# Display.net
KiCad netlist of a schematic drawn in Altium Designer
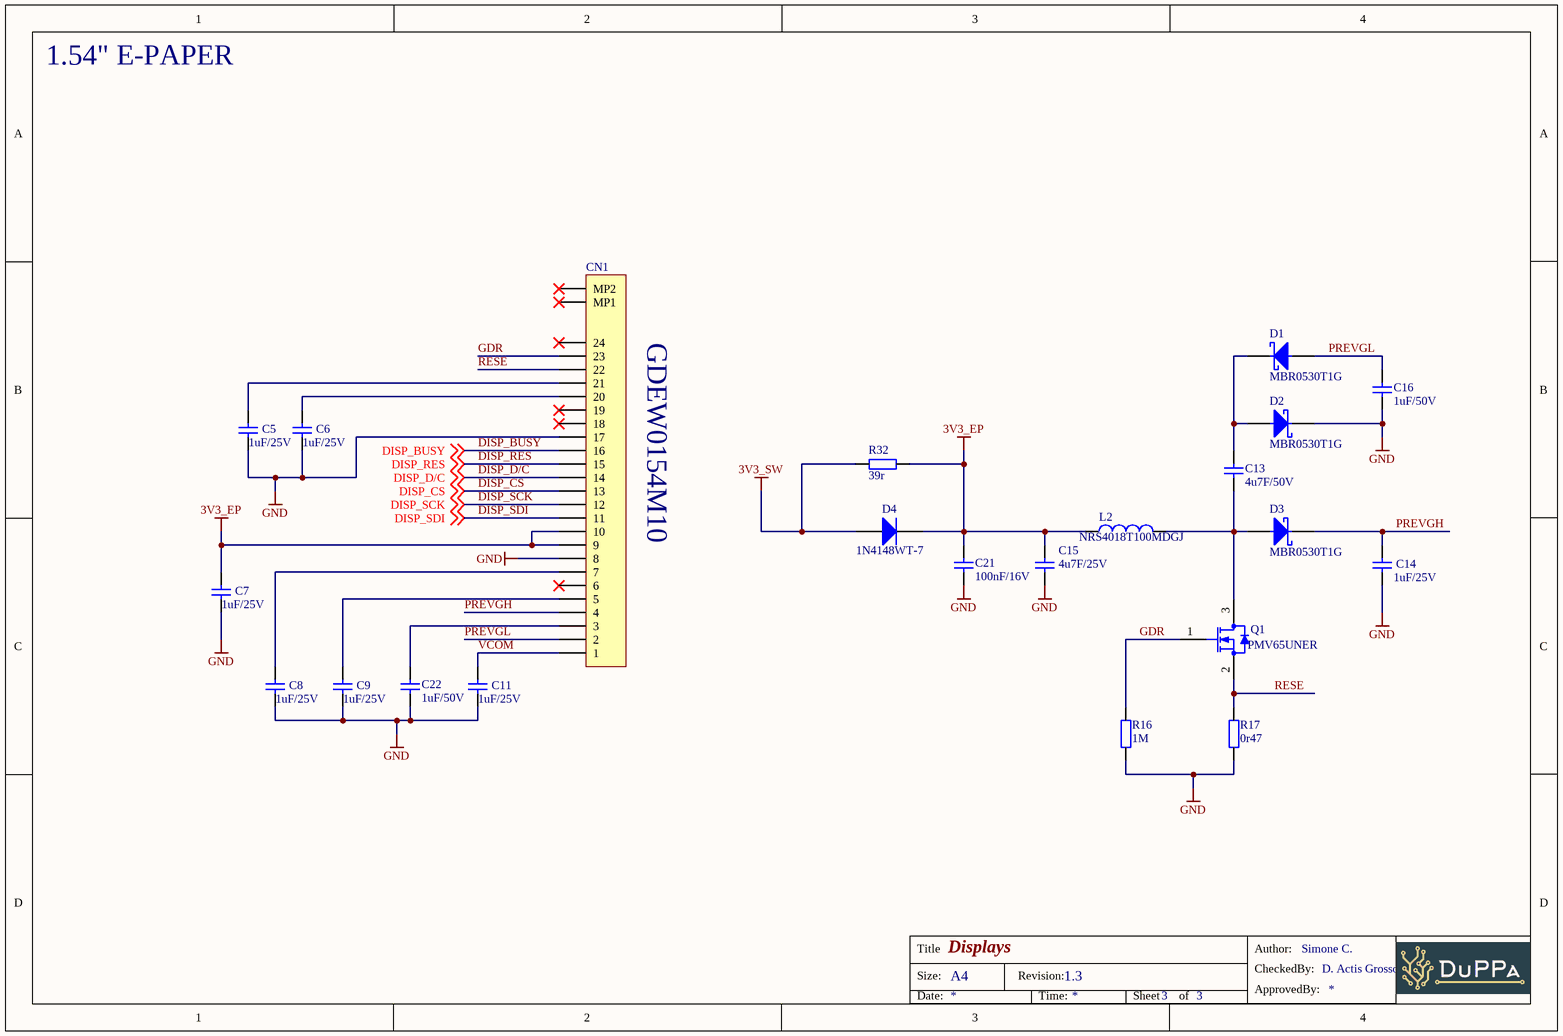
[diagram p0: Display.SchDoc]

(export (version "E")
  (design (tool "Eeschema 10.0.6"))
  (components
    (comp (ref "C5")
      (value "1uF/25V")
      (footprint "C0402")
      (description "1uF ±10% 25V Ceramic Capacitor X5R 0402")
      (fields
        (field (name "PARTNUMBER") "CL05A105KA5NQNC")
        (field (name "MANUFACTURER") "Samsung Electro-Mechanics")
      )
      (libsource (lib "DuPPa_Lib") (part "Cap_0402_1uF/25V"))
    )
    (comp (ref "C6")
      (value "1uF/25V")
      (footprint "C0402")
      (description "1uF ±10% 25V Ceramic Capacitor X5R 0402")
      (fields
        (field (name "PARTNUMBER") "CL05A105KA5NQNC")
        (field (name "MANUFACTURER") "Samsung Electro-Mechanics")
      )
      (libsource (lib "DuPPa_Lib") (part "Cap_0402_1uF/25V"))
    )
    (comp (ref "C7")
      (value "1uF/25V")
      (footprint "C0402")
      (description "1uF ±10% 25V Ceramic Capacitor X5R 0402")
      (fields
        (field (name "PARTNUMBER") "CL05A105KA5NQNC")
        (field (name "MANUFACTURER") "Samsung Electro-Mechanics")
      )
      (libsource (lib "DuPPa_Lib") (part "Cap_0402_1uF/25V"))
    )
    (comp (ref "C8")
      (value "1uF/25V")
      (footprint "C0402")
      (description "1uF ±10% 25V Ceramic Capacitor X5R 0402")
      (fields
        (field (name "PARTNUMBER") "CL05A105KA5NQNC")
        (field (name "MANUFACTURER") "Samsung Electro-Mechanics")
      )
      (libsource (lib "DuPPa_Lib") (part "Cap_0402_1uF/25V"))
    )
    (comp (ref "C9")
      (value "1uF/25V")
      (footprint "C0402")
      (description "1uF ±10% 25V Ceramic Capacitor X5R 0402")
      (fields
        (field (name "PARTNUMBER") "CL05A105KA5NQNC")
        (field (name "MANUFACTURER") "Samsung Electro-Mechanics")
      )
      (libsource (lib "DuPPa_Lib") (part "Cap_0402_1uF/25V"))
    )
    (comp (ref "C11")
      (value "1uF/25V")
      (footprint "C0402")
      (description "1uF ±10% 25V Ceramic Capacitor X5R 0402")
      (fields
        (field (name "PARTNUMBER") "CL05A105KA5NQNC")
        (field (name "MANUFACTURER") "Samsung Electro-Mechanics")
      )
      (libsource (lib "DuPPa_Lib") (part "Cap_0402_1uF/25V"))
    )
    (comp (ref "C13")
      (value "4u7F/50V")
      (footprint "C0805")
      (description "4.7uF ±10% 50V Ceramic Capacitor X5R 0805")
      (fields (field (name "PARTNUMBER") "HGC0805R5475K500NSLJ") (field (name "Comment") "Cap_0805_4u7F/50V"))
      (libsource (lib "DuPPa_Lib") (part "Cap_0805_4u7F/50V"))
    )
    (comp (ref "C14")
      (value "1uF/25V")
      (footprint "C0402")
      (description "1uF ±10% 25V Ceramic Capacitor X5R 0402")
      (fields
        (field (name "PARTNUMBER") "CL05A105KA5NQNC")
        (field (name "MANUFACTURER") "Samsung Electro-Mechanics")
      )
      (libsource (lib "DuPPa_Lib") (part "Cap_0402_1uF/25V"))
    )
    (comp (ref "C15")
      (value "4u7F/25V")
      (footprint "C0603")
      (description "4.7uF ±10% 35V Ceramic Capacitor X5R 0603")
      (fields
        (field (name "PARTNUMBER") "CL10A475KL8NRNC")
        (field (name "MANUFACTURER") "Samsung Electro-Mechanics")
      )
      (libsource (lib "DuPPa_Lib") (part "Cap_0603_4u7F/35V"))
    )
    (comp (ref "C16")
      (value "1uF/50V")
      (footprint "C0603")
      (description "50V 1uF X5R ±10% 0603 Ceramic Capacitors ROHS")
      (fields
        (field (name "PARTNUMBER") "CL10A105KB8NNNC")
        (field (name "MANUFACTURER") "Samsung Electro-Mechanics")
      )
      (libsource (lib "DuPPa_Lib") (part "Cap_0603_1uF/50V"))
    )
    (comp (ref "C21")
      (value "100nF/16V")
      (footprint "C0402")
      (description "16V 100nF X7R ±10% 0402 Multilayer Ceramic Capacitors MLCC - SMD/SMT ROHS")
      (fields
        (field (name "PARTNUMBER") "CL05B104KO5NNNC")
        (field (name "MANUFACTURER") "Samsung Electro-Mechanics")
      )
      (libsource (lib "DuPPa_Lib") (part "Cap_0402_100n/16V"))
    )
    (comp (ref "C22")
      (value "1uF/50V")
      (footprint "C0603")
      (description "50V 1uF X5R ±10% 0603 Ceramic Capacitors ROHS")
      (fields
        (field (name "PARTNUMBER") "CL10A105KB8NNNC")
        (field (name "MANUFACTURER") "Samsung Electro-Mechanics")
      )
      (libsource (lib "DuPPa_Lib") (part "Cap_0603_1uF/50V"))
    )
    (comp (ref "CN1")
      (value "F3311A7H121024E200")
      (footprint "F3311A7H121024E200")
      (fields (field (name "MANUFACTURER") "Amphenol ICC / FCI"))
      (libsource (lib "DuPPa_Lib") (part "F3311A7H121024E200"))
    )
    (comp (ref "D1")
      (value "MBR0530T1G")
      (footprint "FP-SOD123-MFG")
      (description "Diode 30V 500mA Surface Mount SOD-123")
      (fields (field (name "PARTNUMBER") "MBR0530T1G") (field (name "MANUFACTURER") "Onsemi"))
      (libsource (lib "DuPPa_Lib") (part "MBR0530T1G"))
    )
    (comp (ref "D2")
      (value "MBR0530T1G")
      (footprint "FP-SOD123-MFG")
      (description "Diode 30V 500mA Surface Mount SOD-123")
      (fields (field (name "PARTNUMBER") "MBR0530T1G") (field (name "MANUFACTURER") "Onsemi"))
      (libsource (lib "DuPPa_Lib") (part "MBR0530T1G"))
    )
    (comp (ref "D3")
      (value "MBR0530T1G")
      (footprint "FP-SOD123-MFG")
      (description "Diode 30V 500mA Surface Mount SOD-123")
      (fields (field (name "PARTNUMBER") "MBR0530T1G") (field (name "MANUFACTURER") "Onsemi"))
      (libsource (lib "DuPPa_Lib") (part "MBR0530T1G"))
    )
    (comp (ref "D4")
      (value "Diode_1N4148WT")
      (footprint "SODFL160X65-2N")
      (description "Diode Independent 80V 125mA Surface Mount SOD-523")
      (fields (field (name "PARTNUMBER") "1N4148WT-7") (field (name "MANUFACTURER") "Diodes"))
      (libsource (lib "DuPPa_Lib") (part "Diode_1N4148WT"))
    )
    (comp (ref "L2")
      (value "10uH_1.44A_NRS4018T100MDGJ")
      (footprint "FP-NRS4018-MFG")
      (description "1.2A 10uH ±20% 1.3A 150mΩ SMD,4x4mm Fixed Inductors RoHS")
      (fields (field (name "MANUFACTURER") "Taiyo Yuden") (field (name "PART NUMBER") "NRS4018T100MDGJ"))
      (libsource (lib "DuPPa_Lib") (part "10uH_1.44A_NRS4018T100MDGJ"))
    )
    (comp (ref "Q1")
      (value "PMV65UNER")
      (footprint "SOT-23-3")
      (description "N-Channel 20V 2.8A 940mW Surface Mount SOT-23")
      (fields (field (name "MANUFACTURER") "Nexperia"))
      (libsource (lib "DuPPa_Lib") (part "PMV65UNER"))
    )
    (comp (ref "R16")
      (value "1M")
      (footprint "R0402")
      (description "1MΩ ±1% 62.5mW 0402 Thick Film Resistor")
      (fields (field (name "PARTNUMBER") "0402WGF1004TCE") (field (name "MANUFACTURER") "UNI-ROYAL"))
      (libsource (lib "DuPPa_Lib") (part "R_R0402_1M"))
    )
    (comp (ref "R17")
      (value "0r47")
      (footprint "R0402")
      (description "0402, 1% ,63mW")
      (fields (field (name "PARTNUMBER") "RL0402JR-070R47L") (field (name "Comment") "R_R0402_0r47"))
      (libsource (lib "DuPPa_Lib") (part "R_R0402_0r47"))
    )
    (comp (ref "R32")
      (value "39r")
      (footprint "R0402")
      (description "39Ω ±1% 62.5mW 0402 Thick Film Resistor")
      (fields (field (name "PARTNUMBER") "0402WGF390JTCE") (field (name "MANUFACTURER") "UNI-ROYAL"))
      (libsource (lib "DuPPa_Lib") (part "R_R0402_39r"))
    )
  )
  (nets
    (net (code "1") (name "/GDR") (class "Default")
      (node (ref "CN1") (pin "23") (pinfunction "23_23") (pintype "passive"))
      (node (ref "Q1") (pin "1") (pinfunction "G_1") (pintype "passive"))
      (node (ref "R16") (pin "2") (pinfunction "2_2") (pintype "passive"))
    )
    (net (code "2") (name "/PREVGH") (class "Default")
      (node (ref "C14") (pin "1") (pinfunction "1_1") (pintype "passive"))
      (node (ref "CN1") (pin "4") (pinfunction "4_4") (pintype "passive"))
      (node (ref "D3") (pin "K") (pinfunction "K_K") (pintype "passive"))
    )
    (net (code "3") (name "/PREVGL") (class "Default")
      (node (ref "C16") (pin "1") (pinfunction "1_1") (pintype "passive"))
      (node (ref "CN1") (pin "2") (pinfunction "2_2") (pintype "passive"))
      (node (ref "D1") (pin "A") (pinfunction "A_A") (pintype "passive"))
    )
    (net (code "4") (name "/RESE") (class "Default")
      (node (ref "CN1") (pin "22") (pinfunction "22_22") (pintype "passive"))
      (node (ref "Q1") (pin "2") (pinfunction "S_2") (pintype "passive"))
      (node (ref "R17") (pin "2") (pinfunction "2_2") (pintype "passive"))
    )
    (net (code "5") (name "/VCOM") (class "Default")
      (node (ref "C11") (pin "1") (pinfunction "1_1") (pintype "passive"))
      (node (ref "CN1") (pin "1") (pinfunction "1_1") (pintype "passive"))
    )
    (net (code "6") (name "3V3_EP") (class "Default")
      (node (ref "C15") (pin "1") (pinfunction "1_1") (pintype "passive"))
      (node (ref "C21") (pin "1") (pinfunction "1_1") (pintype "passive"))
      (node (ref "C7") (pin "1") (pinfunction "1_1") (pintype "passive"))
      (node (ref "CN1") (pin "10") (pinfunction "10_10") (pintype "passive"))
      (node (ref "CN1") (pin "9") (pinfunction "9_9") (pintype "passive"))
      (node (ref "D4") (pin "K") (pinfunction "K_K") (pintype "passive"))
      (node (ref "L2") (pin "1") (pinfunction "1_1") (pintype "passive"))
      (node (ref "R32") (pin "2") (pinfunction "2_2") (pintype "passive"))
    )
    (net (code "7") (name "3V3_SW") (class "Default")
      (node (ref "D4") (pin "A") (pinfunction "A_A") (pintype "passive"))
      (node (ref "R32") (pin "1") (pinfunction "1_1") (pintype "passive"))
    )
    (net (code "8") (name "DISP_BUSY") (class "Default")
      (node (ref "CN1") (pin "16") (pinfunction "16_16") (pintype "passive"))
    )
    (net (code "9") (name "DISP_CS") (class "Default")
      (node (ref "CN1") (pin "13") (pinfunction "13_13") (pintype "passive"))
    )
    (net (code "10") (name "DISP_D{slash}C") (class "Default")
      (node (ref "CN1") (pin "14") (pinfunction "14_14") (pintype "passive"))
    )
    (net (code "11") (name "DISP_RES") (class "Default")
      (node (ref "CN1") (pin "15") (pinfunction "15_15") (pintype "passive"))
    )
    (net (code "12") (name "DISP_SCK") (class "Default")
      (node (ref "CN1") (pin "12") (pinfunction "12_12") (pintype "passive"))
    )
    (net (code "13") (name "DISP_SDI") (class "Default")
      (node (ref "CN1") (pin "11") (pinfunction "11_11") (pintype "passive"))
    )
    (net (code "14") (name "GND") (class "Default")
      (node (ref "C11") (pin "2") (pinfunction "2_2") (pintype "passive"))
      (node (ref "C14") (pin "2") (pinfunction "2_2") (pintype "passive"))
      (node (ref "C15") (pin "2") (pinfunction "2_2") (pintype "passive"))
      (node (ref "C16") (pin "2") (pinfunction "2_2") (pintype "passive"))
      (node (ref "C21") (pin "2") (pinfunction "2_2") (pintype "passive"))
      (node (ref "C22") (pin "2") (pinfunction "2_2") (pintype "passive"))
      (node (ref "C5") (pin "2") (pinfunction "2_2") (pintype "passive"))
      (node (ref "C6") (pin "2") (pinfunction "2_2") (pintype "passive"))
      (node (ref "C7") (pin "2") (pinfunction "2_2") (pintype "passive"))
      (node (ref "C8") (pin "2") (pinfunction "2_2") (pintype "passive"))
      (node (ref "C9") (pin "2") (pinfunction "2_2") (pintype "passive"))
      (node (ref "CN1") (pin "17") (pinfunction "17_17") (pintype "passive"))
      (node (ref "CN1") (pin "8") (pinfunction "8_8") (pintype "passive"))
      (node (ref "D2") (pin "K") (pinfunction "K_K") (pintype "passive"))
      (node (ref "R16") (pin "1") (pinfunction "1_1") (pintype "passive"))
      (node (ref "R17") (pin "1") (pinfunction "1_1") (pintype "passive"))
    )
    (net (code "15") (name "Net-(C5-Pad1)") (class "Default")
      (node (ref "C5") (pin "1") (pinfunction "1_1") (pintype "passive"))
      (node (ref "CN1") (pin "21") (pinfunction "21_21") (pintype "passive"))
    )
    (net (code "16") (name "Net-(C6-Pad1)") (class "Default")
      (node (ref "C6") (pin "1") (pinfunction "1_1") (pintype "passive"))
      (node (ref "CN1") (pin "20") (pinfunction "20_20") (pintype "passive"))
    )
    (net (code "17") (name "Net-(C8-Pad1)") (class "Default")
      (node (ref "C8") (pin "1") (pinfunction "1_1") (pintype "passive"))
      (node (ref "CN1") (pin "7") (pinfunction "7_7") (pintype "passive"))
    )
    (net (code "18") (name "Net-(C9-Pad1)") (class "Default")
      (node (ref "C9") (pin "1") (pinfunction "1_1") (pintype "passive"))
      (node (ref "CN1") (pin "5") (pinfunction "5_5") (pintype "passive"))
    )
    (net (code "19") (name "Net-(C13-Pad1)") (class "Default")
      (node (ref "C13") (pin "1") (pinfunction "1_1") (pintype "passive"))
      (node (ref "D1") (pin "K") (pinfunction "K_K") (pintype "passive"))
      (node (ref "D2") (pin "A") (pinfunction "A_A") (pintype "passive"))
    )
    (net (code "20") (name "Net-(C22-Pad1)") (class "Default")
      (node (ref "C22") (pin "1") (pinfunction "1_1") (pintype "passive"))
      (node (ref "CN1") (pin "3") (pinfunction "3_3") (pintype "passive"))
    )
    (net (code "21") (name "Net-(Q1-D)") (class "Default")
      (node (ref "C13") (pin "2") (pinfunction "2_2") (pintype "passive"))
      (node (ref "D3") (pin "A") (pinfunction "A_A") (pintype "passive"))
      (node (ref "L2") (pin "2") (pinfunction "2_2") (pintype "passive"))
      (node (ref "Q1") (pin "3") (pinfunction "D_3") (pintype "passive"))
    )
    (net (code "22") (name "unconnected-(CN1-Pad6)") (class "Default")
      (node (ref "CN1") (pin "6") (pinfunction "6_6") (pintype "passive+no_connect"))
    )
    (net (code "23") (name "unconnected-(CN1-Pad18)") (class "Default")
      (node (ref "CN1") (pin "18") (pinfunction "18_18") (pintype "passive+no_connect"))
    )
    (net (code "24") (name "unconnected-(CN1-Pad19)") (class "Default")
      (node (ref "CN1") (pin "19") (pinfunction "19_19") (pintype "passive+no_connect"))
    )
    (net (code "25") (name "unconnected-(CN1-Pad24)") (class "Default")
      (node (ref "CN1") (pin "24") (pinfunction "24_24") (pintype "passive+no_connect"))
    )
    (net (code "26") (name "unconnected-(CN1-PadMP1)") (class "Default")
      (node (ref "CN1") (pin "MP1") (pinfunction "MP1_MP1") (pintype "passive+no_connect"))
    )
    (net (code "27") (name "unconnected-(CN1-PadMP2)") (class "Default")
      (node (ref "CN1") (pin "MP2") (pinfunction "MP2_MP2") (pintype "passive+no_connect"))
    )
  )
)
